# shield_final.net
KiCad netlist of a schematic drawn in EAGLE
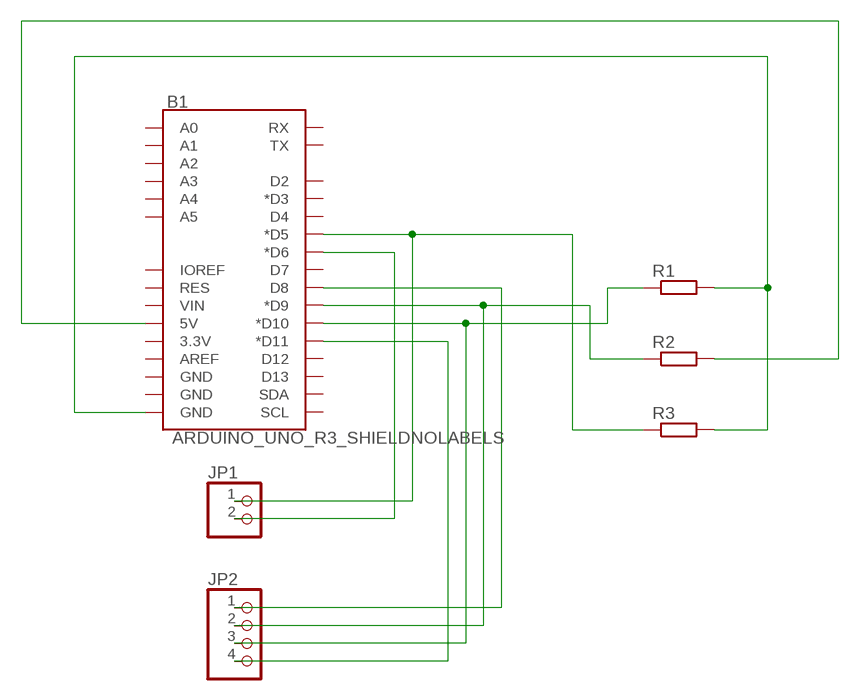
[diagram p0: schematic, sheet 1]

(export (version "E")
  (design (tool "Eeschema 10.0.6"))
  (components
    (comp (ref "B1")
      (value "ARDUINO_UNO_R3_SHIELDNOLABELS")
      (footprint "eagle-import:UNO_R3_SHIELD_NOLABELS")
      (libsource (lib "eagle-import") (part "ARDUINO_UNO_R3_SHIELDNOLABELS"))
    )
    (comp (ref "JP1")
      (value "PINHD-1X2")
      (footprint "eagle-import:1X02")
      (libsource (lib "eagle-import") (part "PINHD-1X2"))
    )
    (comp (ref "JP2")
      (value "PINHD-1X4")
      (footprint "eagle-import:1X04")
      (libsource (lib "eagle-import") (part "PINHD-1X4"))
    )
    (comp (ref "R1")
      (value "R-EU_0207/10")
      (footprint "eagle-import:0207_10")
      (libsource (lib "eagle-import") (part "R-EU_0207/10"))
    )
    (comp (ref "R2")
      (value "R-EU_0207/10")
      (footprint "eagle-import:0207_10")
      (libsource (lib "eagle-import") (part "R-EU_0207/10"))
    )
    (comp (ref "R3")
      (value "R-EU_0207/10")
      (footprint "eagle-import:0207_10")
      (libsource (lib "eagle-import") (part "R-EU_0207/10"))
    )
  )
  (nets
    (net (code "1") (name "Net-(B1-*D5)") (class "Default")
      (node (ref "B1") (pin "D5") (pinfunction "*D5_D5") (pintype "bidirectional"))
      (node (ref "JP1") (pin "1") (pinfunction "1_1") (pintype "passive"))
      (node (ref "R3") (pin "1") (pinfunction "1_1") (pintype "passive"))
    )
    (net (code "2") (name "Net-(B1-*D6)") (class "Default")
      (node (ref "B1") (pin "D6") (pinfunction "*D6_D6") (pintype "bidirectional"))
      (node (ref "JP1") (pin "2") (pinfunction "2_2") (pintype "passive"))
    )
    (net (code "3") (name "Net-(B1-*D9)") (class "Default")
      (node (ref "B1") (pin "D9") (pinfunction "*D9_D9") (pintype "bidirectional"))
      (node (ref "JP2") (pin "2") (pinfunction "2_2") (pintype "passive"))
      (node (ref "R2") (pin "1") (pinfunction "1_1") (pintype "passive"))
    )
    (net (code "4") (name "Net-(B1-*D10)") (class "Default")
      (node (ref "B1") (pin "D10") (pinfunction "*D10_D10") (pintype "bidirectional"))
      (node (ref "JP2") (pin "3") (pinfunction "3_3") (pintype "passive"))
      (node (ref "R1") (pin "1") (pinfunction "1_1") (pintype "passive"))
    )
    (net (code "5") (name "Net-(B1-*D11)") (class "Default")
      (node (ref "B1") (pin "D11") (pinfunction "*D11_D11") (pintype "bidirectional"))
      (node (ref "JP2") (pin "4") (pinfunction "4_4") (pintype "passive"))
    )
    (net (code "6") (name "Net-(B1-GND-PadGND@0)") (class "Default")
      (node (ref "B1") (pin "GND@0") (pinfunction "GND_GND@0") (pintype "bidirectional"))
      (node (ref "R1") (pin "2") (pinfunction "2_2") (pintype "passive"))
      (node (ref "R3") (pin "2") (pinfunction "2_2") (pintype "passive"))
    )
    (net (code "7") (name "Net-(B1-Pad5V)") (class "Default")
      (node (ref "B1") (pin "5V") (pinfunction "5V_5V") (pintype "bidirectional"))
      (node (ref "R2") (pin "2") (pinfunction "2_2") (pintype "passive"))
    )
    (net (code "8") (name "Net-(B1-PadD8)") (class "Default")
      (node (ref "B1") (pin "D8") (pinfunction "D8_D8") (pintype "bidirectional"))
      (node (ref "JP2") (pin "1") (pinfunction "1_1") (pintype "passive"))
    )
    (net (code "9") (name "unconnected-(B1-*D3-PadD3)") (class "Default")
      (node (ref "B1") (pin "D3") (pinfunction "*D3_D3") (pintype "bidirectional"))
    )
    (net (code "10") (name "unconnected-(B1-GND-PadGND@1)") (class "Default")
      (node (ref "B1") (pin "GND@1") (pinfunction "GND_GND@1") (pintype "bidirectional"))
    )
    (net (code "11") (name "unconnected-(B1-GND-PadGND@2)") (class "Default")
      (node (ref "B1") (pin "GND@2") (pinfunction "GND_GND@2") (pintype "bidirectional"))
    )
    (net (code "12") (name "unconnected-(B1-Pad3.3V)") (class "Default")
      (node (ref "B1") (pin "3.3V") (pinfunction "3.3V_3.3V") (pintype "bidirectional"))
    )
    (net (code "13") (name "unconnected-(B1-PadA0)") (class "Default")
      (node (ref "B1") (pin "A0") (pinfunction "A0_A0") (pintype "bidirectional"))
    )
    (net (code "14") (name "unconnected-(B1-PadA1)") (class "Default")
      (node (ref "B1") (pin "A1") (pinfunction "A1_A1") (pintype "bidirectional"))
    )
    (net (code "15") (name "unconnected-(B1-PadA2)") (class "Default")
      (node (ref "B1") (pin "A2") (pinfunction "A2_A2") (pintype "bidirectional"))
    )
    (net (code "16") (name "unconnected-(B1-PadA3)") (class "Default")
      (node (ref "B1") (pin "A3") (pinfunction "A3_A3") (pintype "bidirectional"))
    )
    (net (code "17") (name "unconnected-(B1-PadA4)") (class "Default")
      (node (ref "B1") (pin "A4") (pinfunction "A4_A4") (pintype "bidirectional"))
    )
    (net (code "18") (name "unconnected-(B1-PadA5)") (class "Default")
      (node (ref "B1") (pin "A5") (pinfunction "A5_A5") (pintype "bidirectional"))
    )
    (net (code "19") (name "unconnected-(B1-PadAREF)") (class "Default")
      (node (ref "B1") (pin "AREF") (pinfunction "AREF_AREF") (pintype "bidirectional"))
    )
    (net (code "20") (name "unconnected-(B1-PadD2)") (class "Default")
      (node (ref "B1") (pin "D2") (pinfunction "D2_D2") (pintype "bidirectional"))
    )
    (net (code "21") (name "unconnected-(B1-PadD4)") (class "Default")
      (node (ref "B1") (pin "D4") (pinfunction "D4_D4") (pintype "bidirectional"))
    )
    (net (code "22") (name "unconnected-(B1-PadD7)") (class "Default")
      (node (ref "B1") (pin "D7") (pinfunction "D7_D7") (pintype "bidirectional"))
    )
    (net (code "23") (name "unconnected-(B1-PadD12)") (class "Default")
      (node (ref "B1") (pin "D12") (pinfunction "D12_D12") (pintype "bidirectional"))
    )
    (net (code "24") (name "unconnected-(B1-PadD13)") (class "Default")
      (node (ref "B1") (pin "D13") (pinfunction "D13_D13") (pintype "bidirectional"))
    )
    (net (code "25") (name "unconnected-(B1-PadIOREF)") (class "Default")
      (node (ref "B1") (pin "IOREF") (pinfunction "IOREF_IOREF") (pintype "bidirectional"))
    )
    (net (code "26") (name "unconnected-(B1-PadRES)") (class "Default")
      (node (ref "B1") (pin "RES") (pinfunction "RES_RES") (pintype "bidirectional"))
    )
    (net (code "27") (name "unconnected-(B1-PadRX)") (class "Default")
      (node (ref "B1") (pin "RX") (pinfunction "RX_RX") (pintype "bidirectional"))
    )
    (net (code "28") (name "unconnected-(B1-PadSCL)") (class "Default")
      (node (ref "B1") (pin "SCL") (pinfunction "SCL_SCL") (pintype "bidirectional"))
    )
    (net (code "29") (name "unconnected-(B1-PadSDA)") (class "Default")
      (node (ref "B1") (pin "SDA") (pinfunction "SDA_SDA") (pintype "bidirectional"))
    )
    (net (code "30") (name "unconnected-(B1-PadTX)") (class "Default")
      (node (ref "B1") (pin "TX") (pinfunction "TX_TX") (pintype "bidirectional"))
    )
    (net (code "31") (name "unconnected-(B1-PadVIN)") (class "Default")
      (node (ref "B1") (pin "VIN") (pinfunction "VIN_VIN") (pintype "bidirectional"))
    )
  )
)
